# PAPR_02.net
KiCad netlist of a schematic drawn in EAGLE
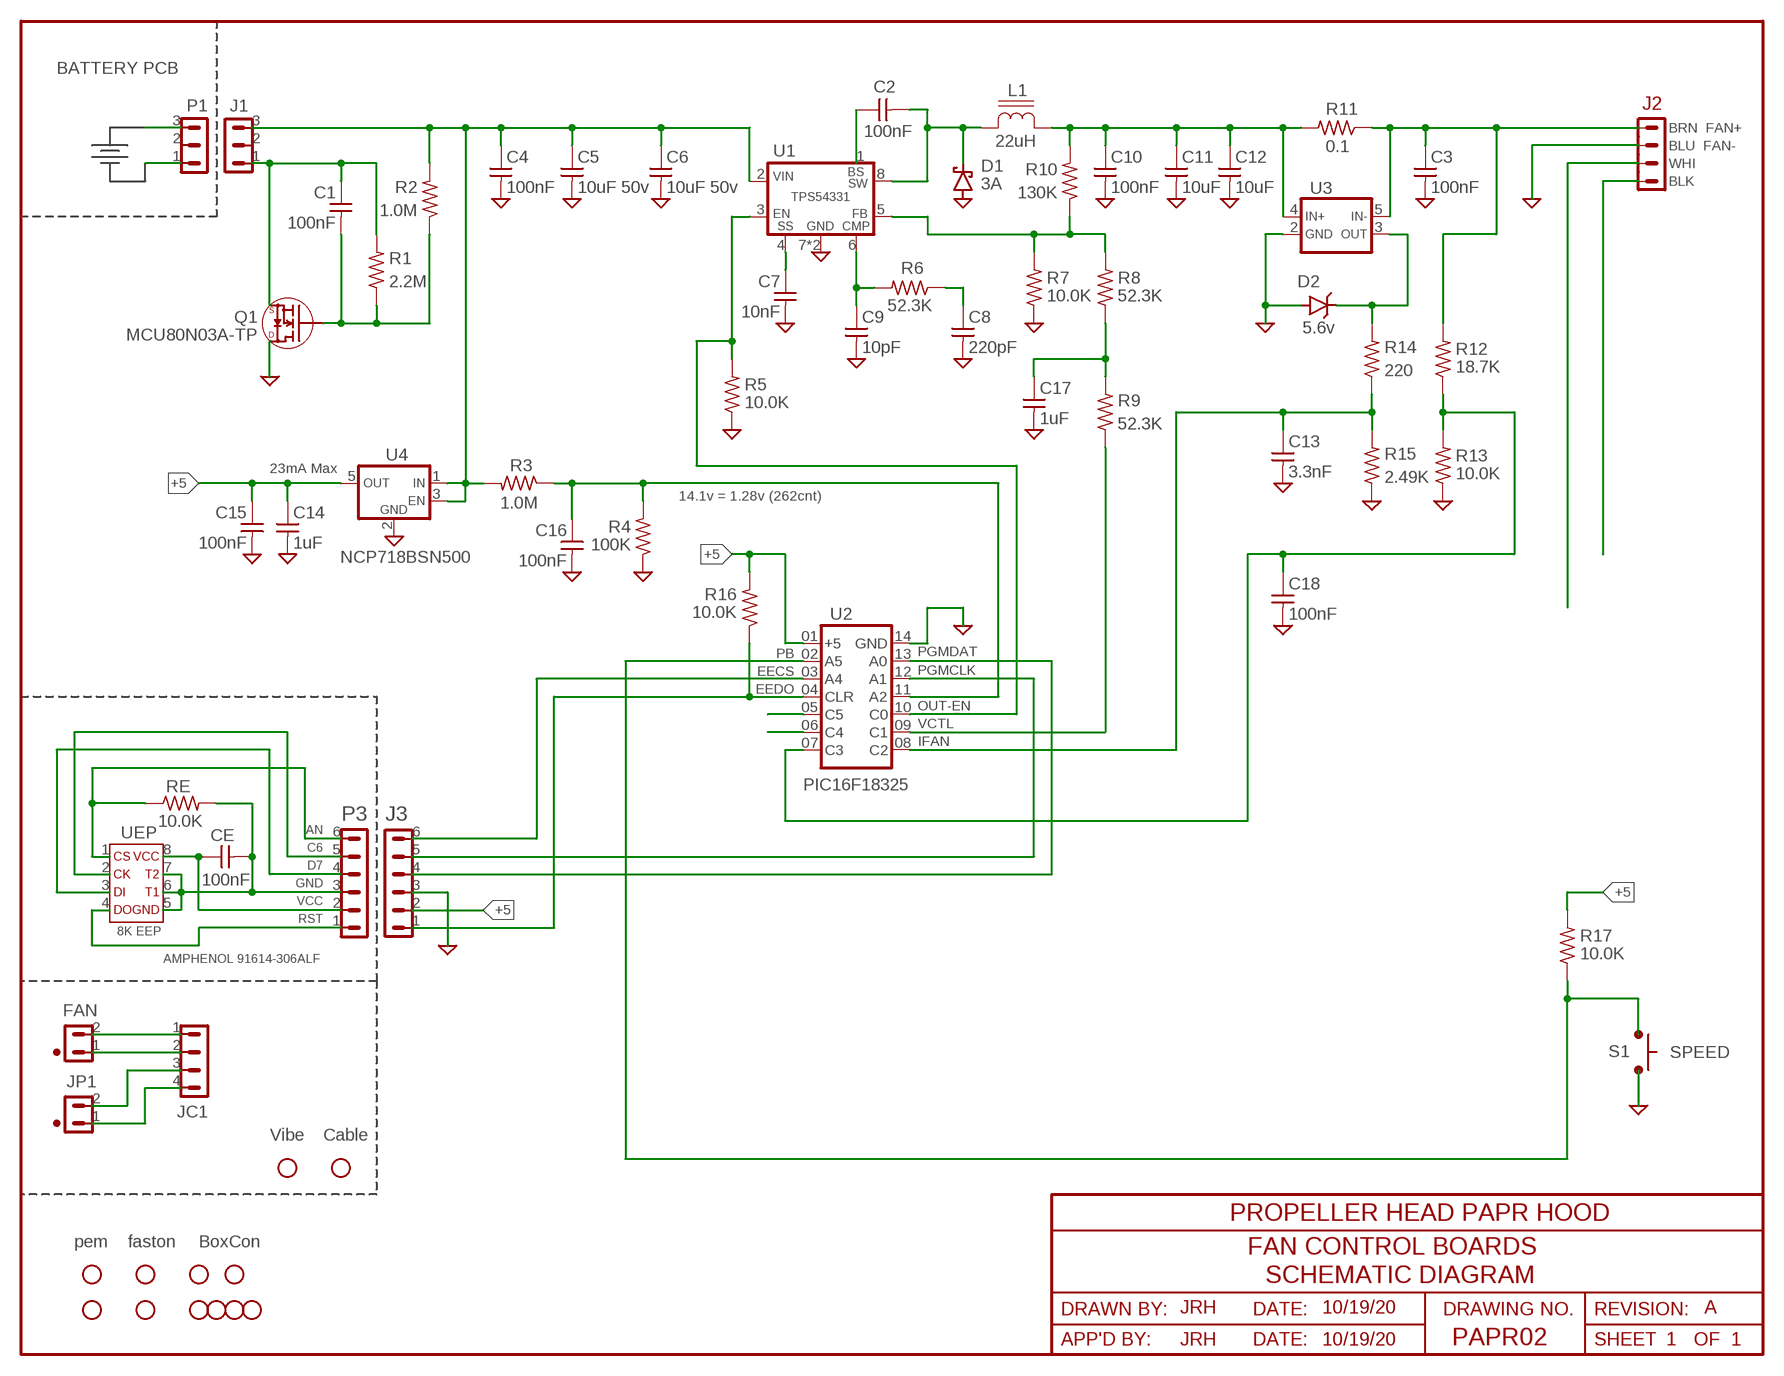
[diagram p0: schematic, sheet 1]

(export (version "E")
  (design (tool "Eeschema 10.0.6"))
  (components
    (comp (ref "BOM1")
      (value "pem")
      (footprint "eagle-import:BOM_ADDER")
      (fields
        (field (name "MFG") "???")
        (field (name "DESC") "PEM Fastener")
        (field (name "MFG_1") "PEM Engineering")
        (field (name "PART_NUMBER") "KF2-440-ET")
        (field (name "PRICE") "0.40")
      )
      (libsource (lib "eagle-import") (part "BOM_ADDER"))
    )
    (comp (ref "BOM2")
      (value "pem")
      (footprint "eagle-import:BOM_ADDER")
      (fields
        (field (name "MFG") "???")
        (field (name "DESC") "PEM Fastener")
        (field (name "MFG_1") "PEM Engineering")
        (field (name "PART_NUMBER") "KF2-440-ET")
        (field (name "PRICE") "0.40")
      )
      (libsource (lib "eagle-import") (part "BOM_ADDER"))
    )
    (comp (ref "BOM3")
      (value "faston")
      (footprint "eagle-import:BOM_ADDER")
      (fields
        (field (name "MFG") "???")
        (field (name "DESC") "Terminal, Faston 0.250")
        (field (name "MFG_1") "Keystone")
        (field (name "PART_NUMBER") "4901")
        (field (name "PRICE") "0.1874")
        (field (name "SUPPLIER") "Digikey 36-4901-ND")
      )
      (libsource (lib "eagle-import") (part "BOM_ADDER"))
    )
    (comp (ref "BOM4")
      (value "faston")
      (footprint "eagle-import:BOM_ADDER")
      (fields
        (field (name "MFG") "???")
        (field (name "DESC") "Terminal, Faston 0.250")
        (field (name "MFG_1") "Keystone")
        (field (name "PART_NUMBER") "4901")
        (field (name "PRICE") "0.1874")
        (field (name "SUPPLIER") "Digikey 36-4901-ND")
      )
      (libsource (lib "eagle-import") (part "BOM_ADDER"))
    )
    (comp (ref "BOM5")
      (value "vibrator")
      (footprint "eagle-import:BOM_ADDER")
      (fields
        (field (name "MFG") "???")
        (field (name "DESC") "Vibrator")
        (field (name "MFG_1") "Jinlong")
        (field (name "PART_NUMBER") "Z6SCAB0061141")
        (field (name "PRICE") "2.657")
        (field (name "SUPPLIER") "Digikey 1670-1021-ND")
      )
      (libsource (lib "eagle-import") (part "BOM_ADDER"))
    )
    (comp (ref "BOM6")
      (value "BoxCon")
      (footprint "eagle-import:BOM_ADDER")
      (fields
        (field (name "MFG") "???")
        (field (name "DESC") "Connector,Circular,4p")
        (field (name "MFG_1") "TE")
        (field (name "PART_NUMBER") "T4070014041-001")
        (field (name "PRICE") "6.9932")
        (field (name "SUPPLIER") "Digikey A126812-ND")
      )
      (libsource (lib "eagle-import") (part "BOM_ADDER"))
    )
    (comp (ref "BOM7")
      (value "Cable")
      (footprint "eagle-import:BOM_ADDER")
      (fields
        (field (name "MFG") "???")
        (field (name "DESC") "Cable,Circular,4p")
        (field (name "MFG_1") "TE")
        (field (name "PART_NUMBER") "1-2273003-1")
        (field (name "PRICE") "10.3224")
        (field (name "SUPPLIER") "Digikey A120949-ND")
      )
      (libsource (lib "eagle-import") (part "BOM_ADDER"))
    )
    (comp (ref "BOM8")
      (value "Plug")
      (footprint "eagle-import:BOM_ADDER")
      (fields
        (field (name "MFG") "???")
        (field (name "DESC") "Plug,4p,MicroMate 3mm c-c")
        (field (name "MFG_1") "TE")
        (field (name "PART_NUMBER") "1445022-4")
        (field (name "PRICE") "0.3464")
        (field (name "SUPPLIER") "Digikey A30260-ND")
      )
      (libsource (lib "eagle-import") (part "BOM_ADDER"))
    )
    (comp (ref "BOM9")
      (value "Pin")
      (footprint "eagle-import:BOM_ADDER")
      (fields
        (field (name "MFG") "???")
        (field (name "DESC") "Terminal,male,MicroMate,gold,30u")
        (field (name "MFG_1") "TE")
        (field (name "PART_NUMBER") "1-794606-1")
        (field (name "PRICE") "0.1049")
        (field (name "SUPPLIER") "Digikey A100439CT-ND")
      )
      (libsource (lib "eagle-import") (part "BOM_ADDER"))
    )
    (comp (ref "BOM10")
      (value "Pin")
      (footprint "eagle-import:BOM_ADDER")
      (fields
        (field (name "MFG") "???")
        (field (name "DESC") "Terminal,male,MicroMate,gold,30u")
        (field (name "MFG_1") "TE")
        (field (name "PART_NUMBER") "1-794606-1")
        (field (name "PRICE") "0.1049")
        (field (name "SUPPLIER") "Digikey A100439CT-ND")
      )
      (libsource (lib "eagle-import") (part "BOM_ADDER"))
    )
    (comp (ref "BOM11")
      (value "Pin")
      (footprint "eagle-import:BOM_ADDER")
      (fields
        (field (name "MFG") "???")
        (field (name "DESC") "Terminal,male,MicroMate,gold,30u")
        (field (name "MFG_1") "TE")
        (field (name "PART_NUMBER") "1-794606-1")
        (field (name "PRICE") "0.1049")
        (field (name "SUPPLIER") "Digikey A100439CT-ND")
      )
      (libsource (lib "eagle-import") (part "BOM_ADDER"))
    )
    (comp (ref "BOM12")
      (value "Pin")
      (footprint "eagle-import:BOM_ADDER")
      (fields
        (field (name "MFG") "???")
        (field (name "DESC") "Terminal,male,MicroMate,gold,30u")
        (field (name "MFG_1") "TE")
        (field (name "PART_NUMBER") "1-794606-1")
        (field (name "PRICE") "0.1049")
        (field (name "SUPPLIER") "Digikey A100439CT-ND")
      )
      (libsource (lib "eagle-import") (part "BOM_ADDER"))
    )
    (comp (ref "C1")
      (value "100nF")
      (footprint "eagle-import:R0805")
      (fields
        (field (name "MFG") "??")
        (field (name "DESC") "Capacitor,100nF,50v, MonoCer,X7R,10%")
        (field (name "MFG_1") "Samsung              AVX")
        (field (name "PART_NUMBER") "CL21B104KBC5PNL             08055C104KAT4A")
        (field (name "SUPPLIER") "Digikey 1276-7000-1-ND    478-10836-1-ND")
      )
      (libsource (lib "eagle-import") (part "C-N0805"))
    )
    (comp (ref "C2")
      (value "100nF")
      (footprint "eagle-import:R0805")
      (fields
        (field (name "MFG") "??")
        (field (name "DESC") "Capacitor,100nF,50v, MonoCer,X7R,10%")
        (field (name "MFG_1") "Samsung              AVX")
        (field (name "PART_NUMBER") "CL21B104KBC5PNL             08055C104KAT4A")
        (field (name "SUPPLIER") "Digikey 1276-7000-1-ND    478-10836-1-ND")
      )
      (libsource (lib "eagle-import") (part "C-N0805"))
    )
    (comp (ref "C3")
      (value "100nF")
      (footprint "eagle-import:R0805")
      (fields
        (field (name "MFG") "??")
        (field (name "DESC") "Capacitor,100nF,50v, MonoCer,X7R,10%")
        (field (name "MFG_1") "Samsung              AVX")
        (field (name "PART_NUMBER") "CL21B104KBC5PNL             08055C104KAT4A")
        (field (name "SUPPLIER") "Digikey 1276-7000-1-ND    478-10836-1-ND")
      )
      (libsource (lib "eagle-import") (part "C-N0805"))
    )
    (comp (ref "C4")
      (value "100nF")
      (footprint "eagle-import:R0805")
      (fields
        (field (name "MFG") "??")
        (field (name "DESC") "Capacitor,100nF,50v, MonoCer,X7R,10%")
        (field (name "MFG_1") "Samsung              AVX")
        (field (name "PART_NUMBER") "CL21B104KBC5PNL             08055C104KAT4A")
        (field (name "SUPPLIER") "Digikey 1276-7000-1-ND    478-10836-1-ND")
      )
      (libsource (lib "eagle-import") (part "C-N0805"))
    )
    (comp (ref "C5")
      (value "10uF 50v")
      (footprint "eagle-import:R1210")
      (fields
        (field (name "MFG") "??")
        (field (name "DESC") "Capacitor,10uF,50v, MonoCer,X7R,10%")
        (field (name "MFG_1") "TDK")
        (field (name "PART_NUMBER") "C3225X7R1H106M250AC")
        (field (name "SUPPLIER") "Digikey 445-14933-1-ND")
      )
      (libsource (lib "eagle-import") (part "C-N1210"))
    )
    (comp (ref "C6")
      (value "10uF 50v")
      (footprint "eagle-import:R1210")
      (fields
        (field (name "MFG") "??")
        (field (name "DESC") "Capacitor,10uF,50v, MonoCer,X7R,10%")
        (field (name "MFG_1") "TDK")
        (field (name "PART_NUMBER") "C3225X7R1H106M250AC")
        (field (name "SUPPLIER") "Digikey 445-14933-1-ND")
      )
      (libsource (lib "eagle-import") (part "C-N1210"))
    )
    (comp (ref "C7")
      (value "10nF")
      (footprint "eagle-import:R0805")
      (fields
        (field (name "MFG") "??")
        (field (name "DESC") "Capacitor,10nF,50v, MonoCer,X7R,10%")
        (field (name "MFG_1") "Samsung              AVX")
        (field (name "PART_NUMBER") "CL21B103KBANNNC        C0805C103K1RAC7210")
        (field (name "SUPPLIER") "Digikey 1276-1015-1-ND")
      )
      (libsource (lib "eagle-import") (part "C-N0805"))
    )
    (comp (ref "C8")
      (value "220pF")
      (footprint "eagle-import:R0805")
      (fields
        (field (name "MFG") "??")
        (field (name "DESC") "Capacitor,220pF,50v, MonoCer,C0G,5%")
        (field (name "MFG_1") "Samsung              Venkel")
        (field (name "PART_NUMBER") "CL21C221JBANNNC         C0805C0G500-221JNE")
        (field (name "SUPPLIER") "Digikey 1276-1164-1-ND")
      )
      (libsource (lib "eagle-import") (part "C-N0805"))
    )
    (comp (ref "C9")
      (value "10pF")
      (footprint "eagle-import:R0805")
      (fields
        (field (name "MFG") "??")
        (field (name "DESC") "Capacitor,10pF,50v, MonoCer,NPO,10%")
        (field (name "MFG_1") "Kemet           Stackpole")
        (field (name "PART_NUMBER") "C0805C100K5GACTU         CML0805C0G100JT50V")
        (field (name "SUPPLIER") "Digikey 399-7975-1-ND")
      )
      (libsource (lib "eagle-import") (part "C-N0805"))
    )
    (comp (ref "C10")
      (value "100nF")
      (footprint "eagle-import:R0805")
      (fields
        (field (name "MFG") "??")
        (field (name "DESC") "Capacitor,100nF,50v, MonoCer,X7R,10%")
        (field (name "MFG_1") "Samsung              AVX")
        (field (name "PART_NUMBER") "CL21B104KBC5PNL             08055C104KAT4A")
        (field (name "SUPPLIER") "Digikey 1276-7000-1-ND    478-10836-1-ND")
      )
      (libsource (lib "eagle-import") (part "C-N0805"))
    )
    (comp (ref "C11")
      (value "10uF")
      (footprint "eagle-import:R1210")
      (fields
        (field (name "MFG") "??")
        (field (name "DESC") "Capacitor,10uF,25v, MonoCer,X7R,10%")
        (field (name "MFG_1") "Samsung        Taiyo Yuden")
        (field (name "PART_NUMBER") "CL32A106KAULNNE         TMK325BJ106KN-T")
        (field (name "SUPPLIER") "Digikey 1276-1854-1-ND       587-5950-1-ND")
      )
      (libsource (lib "eagle-import") (part "C-N1210"))
    )
    (comp (ref "C12")
      (value "10uF")
      (footprint "eagle-import:R1210")
      (fields
        (field (name "MFG") "??")
        (field (name "DESC") "Capacitor,10uF,25v, MonoCer,X7R,10%")
        (field (name "MFG_1") "Samsung        Taiyo Yuden")
        (field (name "PART_NUMBER") "CL32A106KAULNNE         TMK325BJ106KN-T")
        (field (name "SUPPLIER") "Digikey 1276-1854-1-ND       587-5950-1-ND")
      )
      (libsource (lib "eagle-import") (part "C-N1210"))
    )
    (comp (ref "C13")
      (value "3.3nF")
      (footprint "eagle-import:R0805")
      (fields
        (field (name "MFG") "??")
        (field (name "DESC") "Capacitor,3.3nF,50v, MonoCer,X7R,10%")
        (field (name "MFG_1") "Kemet")
        (field (name "PART_NUMBER") "C0805C332K5RACTU")
        (field (name "SUPPLIER") "Digikey 399-1153-1-ND")
      )
      (libsource (lib "eagle-import") (part "C-N0805"))
    )
    (comp (ref "C14")
      (value "1uF")
      (footprint "eagle-import:R0805")
      (fields
        (field (name "MFG") "??")
        (field (name "DESC") "Capacitor,1uF,50v, MonoCer,X7R,10%")
        (field (name "MFG_1") "Samsung             Taiyo Yuden")
        (field (name "PART_NUMBER") "CL21B105KOFNNNG         EMK212B7105KG-T")
        (field (name "SUPPLIER") "Digikey 1276-6471-1-ND")
      )
      (libsource (lib "eagle-import") (part "C-N0805"))
    )
    (comp (ref "C15")
      (value "100nF")
      (footprint "eagle-import:R0805")
      (fields
        (field (name "MFG") "??")
        (field (name "DESC") "Capacitor,100nF,50v, MonoCer,X7R,10%")
        (field (name "MFG_1") "Samsung              AVX")
        (field (name "PART_NUMBER") "CL21B104KBC5PNL             08055C104KAT4A")
        (field (name "SUPPLIER") "Digikey 1276-7000-1-ND    478-10836-1-ND")
      )
      (libsource (lib "eagle-import") (part "C-N0805"))
    )
    (comp (ref "C16")
      (value "100nF")
      (footprint "eagle-import:R0805")
      (fields
        (field (name "MFG") "??")
        (field (name "DESC") "Capacitor,100nF,50v, MonoCer,X7R,10%")
        (field (name "MFG_1") "Samsung              AVX")
        (field (name "PART_NUMBER") "CL21B104KBC5PNL             08055C104KAT4A")
        (field (name "SUPPLIER") "Digikey 1276-7000-1-ND    478-10836-1-ND")
      )
      (libsource (lib "eagle-import") (part "C-N0805"))
    )
    (comp (ref "C17")
      (value "1uF")
      (footprint "eagle-import:R0805")
      (fields
        (field (name "MFG") "??")
        (field (name "DESC") "Capacitor,1uF,50v, MonoCer,X7R,10%")
        (field (name "MFG_1") "Samsung             Taiyo Yuden")
        (field (name "PART_NUMBER") "CL21B105KOFNNNG         EMK212B7105KG-T")
        (field (name "SUPPLIER") "Digikey 1276-6471-1-ND")
      )
      (libsource (lib "eagle-import") (part "C-N0805"))
    )
    (comp (ref "C18")
      (value "100nF")
      (footprint "eagle-import:R0805")
      (fields
        (field (name "MFG") "??")
        (field (name "DESC") "Capacitor,100nF,50v, MonoCer,X7R,10%")
        (field (name "MFG_1") "Samsung              AVX")
        (field (name "PART_NUMBER") "CL21B104KBC5PNL             08055C104KAT4A")
        (field (name "SUPPLIER") "Digikey 1276-7000-1-ND    478-10836-1-ND")
      )
      (libsource (lib "eagle-import") (part "C-N0805"))
    )
    (comp (ref "CE")
      (value "100nF")
      (footprint "eagle-import:R0805")
      (fields
        (field (name "MFG") "??")
        (field (name "DESC") "Capacitor,100nF,50v, MonoCer,X7R,10%")
        (field (name "MFG_1") "Samsung              AVX")
        (field (name "PART_NUMBER") "CL21B104KBC5PNL             08055C104KAT4A")
        (field (name "SUPPLIER") "Digikey 1276-7000-1-ND    478-10836-1-ND")
      )
      (libsource (lib "eagle-import") (part "C-N0805"))
    )
    (comp (ref "D1")
      (value "3A")
      (footprint "eagle-import:SMA")
      (fields
        (field (name "MFG") "??")
        (field (name "DESC") "Diode,3A,40V,Schottky,SMA")
        (field (name "MFG_1") "Diodes Inc        OnSemi         Vishay")
        (field (name "PART_NUMBER") "B340A-13-F          MBRA340T3G          SSA34HE3_A/I")
        (field (name "PRICE") "0.191")
        (field (name "SUPPLIER") "Digikey B340A-FDICT-ND     MBRA340T3GOSCT-ND    SSA34HE3_A/IGICT-ND")
      )
      (libsource (lib "eagle-import") (part "DIODES-1A"))
    )
    (comp (ref "D2")
      (value "5.6v")
      (footprint "eagle-import:SOT23-3")
      (fields
        (field (name "MFG") "NXP")
        (field (name "PART_NUMBER") "BZX84-BxVx")
        (field (name "DESC") "Zener,5.6v,250mW,SOT23-3")
        (field (name "MFG_1") "On Semi")
        (field (name "PART_NUMBER_1") "SZBZX84-C5V6LT1G")
        (field (name "PRICE") "0.118")
        (field (name "SUPPLIER") "Digikey SZBZX84C5V6LT1GOSCT-ND")
      )
      (libsource (lib "eagle-import") (part "ZENER3"))
    )
    (comp (ref "FAN")
      (value "Fan_Hdr")
      (footprint "eagle-import:641215-2")
      (fields (field (name "MFG") "Tyco") (field (name "PART_NUMBER") "641215-2"))
      (libsource (lib "eagle-import") (part "HDR02V"))
    )
    (comp (ref "J1")
      (value "bat")
      (footprint "eagle-import:1746142")
      (fields (field (name "MFG") "TI") (field (name "PART_NUMBER") "1745142-1"))
      (libsource (lib "eagle-import") (part "HDR03_17"))
    )
    (comp (ref "J2-BLK")
      (value "WIRE-HDRS200")
      (footprint "eagle-import:PADS200")
      (fields (field (name "MFG") "??"))
      (libsource (lib "eagle-import") (part "WIRE-HDRS200"))
    )
    (comp (ref "J2-BLU")
      (value "WIRE-HDRS200")
      (footprint "eagle-import:PADS200")
      (fields (field (name "MFG") "??"))
      (libsource (lib "eagle-import") (part "WIRE-HDRS200"))
    )
    (comp (ref "J2-BRN")
      (value "WIRE-HDRS200")
      (footprint "eagle-import:PADS200")
      (fields (field (name "MFG") "??"))
      (libsource (lib "eagle-import") (part "WIRE-HDRS200"))
    )
    (comp (ref "J2-WHI")
      (value "WIRE-HDRS200")
      (footprint "eagle-import:PADS200")
      (fields (field (name "MFG") "??"))
      (libsource (lib "eagle-import") (part "WIRE-HDRS200"))
    )
    (comp (ref "J3")
      (value "6p")
      (footprint "eagle-import:J06P")
      (fields
        (field (name "MFG") "??")
        (field (name "DESC") "Header,6p,thru,gold,8.89mm")
        (field (name "MFG_1") "Samtec")
        (field (name "PART_NUMBER") "MTSW-106-22-G-S-350")
        (field (name "PRICE") "0.750")
        (field (name "SUPPLIER") "Digikey MTSW-106-22-G-S-350-ND")
      )
      (libsource (lib "eagle-import") (part "HDR06R"))
    )
    (comp (ref "JC1")
      (value "Cable_Termination")
      (footprint "eagle-import:B4P-VH")
      (fields (field (name "MFG") "JST") (field (name "PART_NUMBER") "B4P-VH"))
      (libsource (lib "eagle-import") (part "HDR04_JST_B4P-VH"))
    )
    (comp (ref "JP1")
      (value "Spare")
      (footprint "eagle-import:641215-2")
      (fields (field (name "MFG") "Tyco") (field (name "PART_NUMBER") "641215-2"))
      (libsource (lib "eagle-import") (part "HDR02V"))
    )
    (comp (ref "L1")
      (value "22uH")
      (footprint "eagle-import:SRU1048")
      (fields
        (field (name "MFG") "Bourns")
        (field (name "PART_NUMBER") "SDR1048-")
        (field (name "PRICE") "0.6756")
        (field (name "SUPPLIER") "Digikey SRU1048-220YCT-ND")
      )
      (libsource (lib "eagle-import") (part "COIL1048"))
    )
    (comp (ref "P1")
      (value "bat")
      (footprint "eagle-import:1746142M")
      (fields (field (name "MFG") "TI") (field (name "PART_NUMBER") "1745142-1 Mate"))
      (libsource (lib "eagle-import") (part "HDR03_17M"))
    )
    (comp (ref "P3")
      (value "6p plug")
      (footprint "eagle-import:J06P")
      (fields (field (name "MFG") "??"))
      (libsource (lib "eagle-import") (part "HDR06R"))
    )
    (comp (ref "Q1")
      (value "MCU80N03A-TP")
      (footprint "eagle-import:TO252")
      (fields
        (field (name "MFG") "??")
        (field (name "DESC") "MOSFET,N-Ch,30v,<18m")
        (field (name "MFG_1") "MCC                  Diodes Inc           On Semi")
        (field (name "PART_NUMBER") "MCU80N03A-TP           DMG4800LK3-13             NTD4969NT4G")
        (field (name "PRICE") "0.40")
        (field (name "SUPPLIER") "Digikey 353-MCU80N03A-TPCT-ND")
      )
      (libsource (lib "eagle-import") (part "IGFETNM"))
    )
    (comp (ref "R1")
      (value "2.2M")
      (footprint "eagle-import:R0805")
      (fields
        (field (name "MFG") "Vishay")
        (field (name "PART_NUMBER") "CRCW0805xxxFKEA")
        (field (name "DESC") "Resistor,2.2M,1/8w,1%")
        (field (name "MFG_1") "Stackpole             Vishay")
        (field (name "PART_NUMBER_1") "RMCF0805FT2M21          CRCW08052M20FKEA")
        (field (name "SUPPLIER") "Digikey RMCF0805FT2M21CT-ND")
      )
      (libsource (lib "eagle-import") (part "R0805"))
    )
    (comp (ref "R2")
      (value "1.0M")
      (footprint "eagle-import:R0805")
      (fields
        (field (name "MFG") "Vishay")
        (field (name "PART_NUMBER") "CRCW0805xxxFKEA")
        (field (name "DESC") "Resistor,1.0M,1/8w,1%")
        (field (name "MFG_1") "Stackpole              KOA Speer")
        (field (name "PART_NUMBER_1") "RMCF0805FG1M00          RK73H2ATTD1004F")
        (field (name "SUPPLIER") "Digikey RMCF0805FG1M00CT-ND       2019-RK73H2ATTD1004FCT-ND")
      )
      (libsource (lib "eagle-import") (part "R0805"))
    )
    (comp (ref "R3")
      (value "1.0M")
      (footprint "eagle-import:R0805")
      (fields
        (field (name "MFG") "Vishay")
        (field (name "PART_NUMBER") "CRCW0805xxxFKEA")
        (field (name "DESC") "Resistor,1.0M,1/8w,1%")
        (field (name "MFG_1") "Stackpole             Vishay")
        (field (name "PART_NUMBER_1") "RMCF0805FT2M21          CRCW08052M20FKEA")
        (field (name "SUPPLIER") "Digikey RMCF0805FT2M21CT-ND       541-2.20MCCT-ND")
      )
      (libsource (lib "eagle-import") (part "R0805"))
    )
    (comp (ref "R4")
      (value "100K")
      (footprint "eagle-import:R0805")
      (fields
        (field (name "MFG") "Vishay")
        (field (name "PART_NUMBER") "CRCW0805xxxFKEA")
        (field (name "DESC") "Resistor,100K,1/8w,1%")
        (field (name "MFG_1") "Stackpole             KOA Speer")
        (field (name "PART_NUMBER_1") "RMCF0805FG100K          RK73H2ATTD1003F")
        (field (name "SUPPLIER") "Digikey RMCF0805FT100KTR-ND")
      )
      (libsource (lib "eagle-import") (part "R0805"))
    )
    (comp (ref "R5")
      (value "10.0K")
      (footprint "eagle-import:R0805")
      (fields
        (field (name "MFG") "Vishay")
        (field (name "PART_NUMBER") "CRCW0805xxxFKEA")
        (field (name "DESC") "Resistor,10.0K,1/8w,1%")
        (field (name "MFG_1") "Stackpole             KOA Speer")
        (field (name "PART_NUMBER_1") "RMCF0805FT10K0          RK73H2ATTD1002F")
        (field (name "SUPPLIER") "Digikey RMCF0805FT10K0CT-ND")
      )
      (libsource (lib "eagle-import") (part "R0805"))
    )
    (comp (ref "R6")
      (value "52.3K")
      (footprint "eagle-import:R0805")
      (fields
        (field (name "MFG") "Vishay")
        (field (name "PART_NUMBER") "CRCW0805xxxFKEA")
        (field (name "DESC") "Resistor,52.3K,1/8w,1%")
        (field (name "MFG_1") "Yageo          Vishay")
        (field (name "PART_NUMBER_1") "RC0805FR-0752K3L        CRCW080552K3FKEA")
        (field (name "SUPPLIER") "Digikey 311-52.3KCRCT-ND")
      )
      (libsource (lib "eagle-import") (part "R0805"))
    )
    (comp (ref "R7")
      (value "10.0K")
      (footprint "eagle-import:R0805")
      (fields
        (field (name "MFG") "Vishay")
        (field (name "PART_NUMBER") "CRCW0805xxxFKEA")
        (field (name "DESC") "Resistor,10.0K,1/8w,1%")
        (field (name "MFG_1") "Stackpole             KOA Speer")
        (field (name "PART_NUMBER_1") "RMCF0805FT10K0          RK73H2ATTD1002F")
        (field (name "SUPPLIER") "Digikey RMCF0805FT10K0CT-ND")
      )
      (libsource (lib "eagle-import") (part "R0805"))
    )
    (comp (ref "R8")
      (value "52.3K")
      (footprint "eagle-import:R0805")
      (fields
        (field (name "MFG") "Vishay")
        (field (name "PART_NUMBER") "CRCW0805xxxFKEA")
        (field (name "DESC") "Resistor,52.3K,1/8w,1%")
        (field (name "MFG_1") "Yageo          Vishay")
        (field (name "PART_NUMBER_1") "RC0805FR-0752K3L        CRCW080552K3FKEA")
        (field (name "SUPPLIER") "Digikey 311-52.3KCRCT-ND")
      )
      (libsource (lib "eagle-import") (part "R0805"))
    )
    (comp (ref "R9")
      (value "52.3K")
      (footprint "eagle-import:R0805")
      (fields
        (field (name "MFG") "Vishay")
        (field (name "PART_NUMBER") "CRCW0805xxxFKEA")
        (field (name "DESC") "Resistor,52.3K,1/8w,1%")
        (field (name "MFG_1") "Yageo          Vishay")
        (field (name "PART_NUMBER_1") "RC0805FR-0752K3L        CRCW080552K3FKEA")
        (field (name "SUPPLIER") "Digikey 311-52.3KCRCT-ND")
      )
      (libsource (lib "eagle-import") (part "R0805"))
    )
    (comp (ref "R10")
      (value "130K")
      (footprint "eagle-import:R0805")
      (fields
        (field (name "MFG") "Vishay")
        (field (name "PART_NUMBER") "CRCW0805xxxFKEA")
        (field (name "DESC") "Resistor,130K,1/8w,1%")
        (field (name "MFG_1") "KOA Speer         Yageo")
        (field (name "PART_NUMBER_1") "RK73H2ATTD1303F         RC0805FR-07130KL")
        (field (name "SUPPLIER") "Digikey 2019-RK73H2ATTD1303FCT-ND")
      )
      (libsource (lib "eagle-import") (part "R0805"))
    )
    (comp (ref "R11")
      (value "0.1")
      (footprint "eagle-import:R2512")
      (fields
        (field (name "MFG") "Vishay")
        (field (name "PART_NUMBER") "CRCW2512xxxFKEA")
        (field (name "DESC") "Resistor,0.1,2w,1%")
        (field (name "MFG_1") "Stackpole")
        (field (name "PART_NUMBER_1") "CSRN2512FTR100")
        (field (name "SUPPLIER") "Digikey CSRN2512FTR100CT-ND")
      )
      (libsource (lib "eagle-import") (part "R2512"))
    )
    (comp (ref "R12")
      (value "18.7K")
      (footprint "eagle-import:R0805")
      (fields
        (field (name "MFG") "Vishay")
        (field (name "PART_NUMBER") "CRCW0805xxxFKEA")
        (field (name "DESC") "Resistor,18.7K,1/8w,1%")
        (field (name "MFG_1") "Stackpole             Yageo")
        (field (name "PART_NUMBER_1") "RMCF0805FT18K7          RC0805FR0718K7L")
        (field (name "SUPPLIER") "Digikey RMCF0805FT18K7CT-ND")
      )
      (libsource (lib "eagle-import") (part "R0805"))
    )
    (comp (ref "R13")
      (value "10.0K")
      (footprint "eagle-import:R0805")
      (fields
        (field (name "MFG") "Vishay")
        (field (name "PART_NUMBER") "CRCW0805xxxFKEA")
        (field (name "DESC") "Resistor,10.0K,1/8w,1%")
        (field (name "MFG_1") "Stackpole             KOA Speer")
        (field (name "PART_NUMBER_1") "RMCF0805FT10K0          RK73H2ATTD1002F")
        (field (name "SUPPLIER") "Digikey RMCF0805FT10K0CT-ND")
      )
      (libsource (lib "eagle-import") (part "R0805"))
    )
    (comp (ref "R14")
      (value "220")
      (footprint "eagle-import:R0805")
      (fields
        (field (name "MFG") "Vishay")
        (field (name "PART_NUMBER") "CRCW0805xxxFKEA")
        (field (name "DESC") "Resistor,220,1/8w,1%")
        (field (name "MFG_1") "Stackpole             KOA Speer")
        (field (name "PART_NUMBER_1") "RMCF0805FT220R          RK73H2ATTD2200F")
        (field (name "SUPPLIER") "Digikey RMCF0805FT220RCT-ND")
      )
      (libsource (lib "eagle-import") (part "R0805"))
    )
    (comp (ref "R15")
      (value "2.49K")
      (footprint "eagle-import:R0805")
      (fields
        (field (name "MFG") "Vishay")
        (field (name "PART_NUMBER") "CRCW0805xxxFKEA")
        (field (name "DESC") "Resistor,2.49K,1/8w,1%")
        (field (name "MFG_1") "Stackpole             Vishay")
        (field (name "PART_NUMBER_1") "RMCF0805FT2K49          CRCW08052K49FKEA")
        (field (name "SUPPLIER") "Digikey RMCF0805FT2K49CT-ND")
      )
      (libsource (lib "eagle-import") (part "R0805"))
    )
    (comp (ref "R16")
      (value "10.0K")
      (footprint "eagle-import:R0805")
      (fields
        (field (name "MFG") "Vishay")
        (field (name "PART_NUMBER") "CRCW0805xxxFKEA")
        (field (name "DESC") "Resistor,10.0K,1/8w,1%")
        (field (name "MFG_1") "Stackpole             KOA Speer")
        (field (name "PART_NUMBER_1") "RMCF0805FT10K0          RK73H2ATTD1002F")
        (field (name "SUPPLIER") "Digikey RMCF0805FT10K0CT-ND")
      )
      (libsource (lib "eagle-import") (part "R0805"))
    )
    (comp (ref "R17")
      (value "10.0K")
      (footprint "eagle-import:R0805")
      (fields
        (field (name "MFG") "Vishay")
        (field (name "PART_NUMBER") "CRCW0805xxxFKEA")
        (field (name "DESC") "Resistor,10.0K,1/8w,1%")
        (field (name "MFG_1") "Stackpole             KOA Speer")
        (field (name "PART_NUMBER_1") "RMCF0805FT10K0          RK73H2ATTD1002F")
        (field (name "SUPPLIER") "Digikey RMCF0805FT10K0CT-ND")
      )
      (libsource (lib "eagle-import") (part "R0805"))
    )
    (comp (ref "RE")
      (value "10.0K")
      (footprint "eagle-import:R0805")
      (fields
        (field (name "MFG") "Vishay")
        (field (name "PART_NUMBER") "CRCW0805xxxFKEA")
        (field (name "DESC") "Resistor,10.0K,1/8w,1%")
        (field (name "MFG_1") "Stackpole             KOA Speer")
        (field (name "PART_NUMBER_1") "RMCF0805FT10K0          RK73H2ATTD1002F")
        (field (name "SUPPLIER") "Digikey RMCF0805FT10K0CT-ND")
      )
      (libsource (lib "eagle-import") (part "R0805"))
    )
    (comp (ref "S1")
      (value "SPEED")
      (footprint "eagle-import:EVQ-P7C01P")
      (fields (field (name "MFG") "Panasonic") (field (name "PART_NUMBER") "EVQ-P7C01P"))
      (libsource (lib "eagle-import") (part "PUSHBUTTONQ"))
    )
    (comp (ref "U1")
      (value "TPS54331")
      (footprint "eagle-import:SO08PW")
      (fields
        (field (name "MFG") "TI")
        (field (name "PART_NUMBER") "TPS54331DDAR")
        (field (name "PRICE") "1.352")
      )
      (libsource (lib "eagle-import") (part "TPS54331DDAR"))
    )
    (comp (ref "U2")
      (value "PIC16F18325")
      (footprint "eagle-import:SOIC14")
      (fields
        (field (name "MFG") "Microchip")
        (field (name "PART_NUMBER") "PIC16F616-I/SL")
        (field (name "PART_NUMBER_1") "PIC16F18325-I/SL")
        (field (name "SUPPLIER") "Digikey PIC16F18325-I/SL-ND")
      )
      (libsource (lib "eagle-import") (part "PIC16F616/SL-I"))
    )
    (comp (ref "U3")
      (value "ZXCT1010")
      (footprint "eagle-import:SOT23-5")
      (fields (field (name "MFG") "DiodesInc") (field (name "PART_NUMBER") "ZXCT1010E5TA"))
      (libsource (lib "eagle-import") (part "ZXCT1010E5TA"))
    )
    (comp (ref "U4")
      (value "NCP718BSN500")
      (footprint "eagle-import:SOT23-5")
      (fields
        (field (name "MFG") "T.I.")
        (field (name "PART_NUMBER") "LP2981-50DBVR or BVT")
        (field (name "DESC") "Regulator,LoQ,5.0v,25vIn")
        (field (name "MFG_1") "On Semi")
        (field (name "PART_NUMBER_1") "NCP718BSN500T1G")
        (field (name "SUPPLIER") "Digikey NCP718BSN500T1GOSCT-ND")
      )
      (libsource (lib "eagle-import") (part "LP2981AIM"))
    )
    (comp (ref "UEP")
      (value "4K EEP")
      (footprint "eagle-import:SO08")
      (fields (field (name "MFG") "ROHM Semi") (field (name "PART_NUMBER") "BR93H76RFJ-2CE"))
      (libsource (lib "eagle-import") (part "BR93H76RFJ-2CE"))
    )
  )
  (nets
    (net (code "1") (name "+5") (class "Default")
      (node (ref "C14") (pin "1") (pinfunction "1_1") (pintype "passive"))
      (node (ref "C15") (pin "1") (pinfunction "1_1") (pintype "passive"))
      (node (ref "J3") (pin "2") (pinfunction "2_2") (pintype "passive"))
      (node (ref "R16") (pin "1") (pinfunction "1_1") (pintype "passive"))
      (node (ref "R17") (pin "1") (pinfunction "1_1") (pintype "passive"))
      (node (ref "U2") (pin "01") (pinfunction "VCC_01") (pintype "input"))
      (node (ref "U4") (pin "5") (pinfunction "OUT_5") (pintype "output"))
    )
    (net (code "2") (name "/EECS") (class "Default")
      (node (ref "J3") (pin "6") (pinfunction "6_6") (pintype "passive"))
      (node (ref "U2") (pin "03") (pinfunction "A4_03") (pintype "bidirectional"))
    )
    (net (code "3") (name "/EEDO") (class "Default")
      (node (ref "J3") (pin "1") (pinfunction "1_1") (pintype "passive"))
      (node (ref "R16") (pin "2") (pinfunction "2_2") (pintype "passive"))
      (node (ref "U2") (pin "04") (pinfunction "CLR_04") (pintype "input"))
    )
    (net (code "4") (name "/IFAN") (class "Default")
      (node (ref "C13") (pin "1") (pinfunction "1_1") (pintype "passive"))
      (node (ref "R14") (pin "2") (pinfunction "2_2") (pintype "passive"))
      (node (ref "R15") (pin "1") (pinfunction "1_1") (pintype "passive"))
      (node (ref "U2") (pin "08") (pinfunction "C2_08") (pintype "bidirectional"))
    )
    (net (code "5") (name "/OUT-EN") (class "Default")
      (node (ref "R5") (pin "1") (pinfunction "1_1") (pintype "passive"))
      (node (ref "U1") (pin "3") (pinfunction "EN_3") (pintype "input"))
      (node (ref "U2") (pin "10") (pinfunction "C0_10") (pintype "bidirectional"))
    )
    (net (code "6") (name "/PB") (class "Default")
      (node (ref "R17") (pin "2") (pinfunction "2_2") (pintype "passive"))
      (node (ref "S1") (pin "3") (pinfunction "2_3") (pintype "passive"))
      (node (ref "S1") (pin "4") (pinfunction "2_4") (pintype "passive"))
      (node (ref "U2") (pin "02") (pinfunction "A5_02") (pintype "bidirectional"))
    )
    (net (code "7") (name "/PGMCLK") (class "Default")
      (node (ref "J3") (pin "5") (pinfunction "5_5") (pintype "passive"))
      (node (ref "U2") (pin "12") (pinfunction "A1_12") (pintype "bidirectional"))
    )
    (net (code "8") (name "/PGMDAT") (class "Default")
      (node (ref "J3") (pin "4") (pinfunction "4_4") (pintype "passive"))
      (node (ref "U2") (pin "13") (pinfunction "A0_13") (pintype "bidirectional"))
    )
    (net (code "9") (name "/VCTL") (class "Default")
      (node (ref "R9") (pin "2") (pinfunction "2_2") (pintype "passive"))
      (node (ref "U2") (pin "09") (pinfunction "C1_09") (pintype "bidirectional"))
    )
    (net (code "10") (name "GND") (class "Default")
      (node (ref "C10") (pin "2") (pinfunction "2_2") (pintype "passive"))
      (node (ref "C11") (pin "2") (pinfunction "2_2") (pintype "passive"))
      (node (ref "C12") (pin "2") (pinfunction "2_2") (pintype "passive"))
      (node (ref "C13") (pin "2") (pinfunction "2_2") (pintype "passive"))
      (node (ref "C14") (pin "2") (pinfunction "2_2") (pintype "passive"))
      (node (ref "C15") (pin "2") (pinfunction "2_2") (pintype "passive"))
      (node (ref "C16") (pin "2") (pinfunction "2_2") (pintype "passive"))
      (node (ref "C17") (pin "2") (pinfunction "2_2") (pintype "passive"))
      (node (ref "C18") (pin "2") (pinfunction "2_2") (pintype "passive"))
      (node (ref "C3") (pin "2") (pinfunction "2_2") (pintype "passive"))
      (node (ref "C4") (pin "2") (pinfunction "2_2") (pintype "passive"))
      (node (ref "C5") (pin "2") (pinfunction "2_2") (pintype "passive"))
      (node (ref "C6") (pin "2") (pinfunction "2_2") (pintype "passive"))
      (node (ref "C7") (pin "2") (pinfunction "2_2") (pintype "passive"))
      (node (ref "C8") (pin "2") (pinfunction "2_2") (pintype "passive"))
      (node (ref "C9") (pin "2") (pinfunction "2_2") (pintype "passive"))
      (node (ref "D1") (pin "A") (pinfunction "A_A") (pintype "passive"))
      (node (ref "D2") (pin "1") (pinfunction "A_1") (pintype "passive"))
      (node (ref "J2-BLU") (pin "1") (pinfunction "1_1") (pintype "passive"))
      (node (ref "J3") (pin "3") (pinfunction "3_3") (pintype "passive"))
      (node (ref "Q1") (pin "3") (pinfunction "D_3") (pintype "passive"))
      (node (ref "R13") (pin "2") (pinfunction "2_2") (pintype "passive"))
      (node (ref "R15") (pin "2") (pinfunction "2_2") (pintype "passive"))
      (node (ref "R4") (pin "2") (pinfunction "2_2") (pintype "passive"))
      (node (ref "R5") (pin "2") (pinfunction "2_2") (pintype "passive"))
      (node (ref "R7") (pin "2") (pinfunction "2_2") (pintype "passive"))
      (node (ref "S1") (pin "1") (pinfunction "1_1") (pintype "passive"))
      (node (ref "S1") (pin "2") (pinfunction "1_2") (pintype "passive"))
      (node (ref "U1") (pin "7") (pinfunction "GND_7") (pintype "input"))
      (node (ref "U1") (pin "9") (pinfunction "GND_9") (pintype "input"))
      (node (ref "U2") (pin "14") (pinfunction "GND_14") (pintype "input"))
      (node (ref "U3") (pin "2") (pinfunction "GND_2") (pintype "input"))
      (node (ref "U4") (pin "2") (pinfunction "GND_2") (pintype "input"))
    )
    (net (code "11") (name "Net-(C8-Pad1)") (class "Default")
      (node (ref "C8") (pin "1") (pinfunction "1_1") (pintype "passive"))
      (node (ref "R6") (pin "2") (pinfunction "2_2") (pintype "passive"))
    )
    (net (code "12") (name "Net-(C17-Pad1)") (class "Default")
      (node (ref "C17") (pin "1") (pinfunction "1_1") (pintype "passive"))
      (node (ref "R8") (pin "2") (pinfunction "2_2") (pintype "passive"))
      (node (ref "R9") (pin "1") (pinfunction "1_1") (pintype "passive"))
    )
    (net (code "13") (name "Net-(D2-C)") (class "Default")
      (node (ref "D2") (pin "3") (pinfunction "C_3") (pintype "passive"))
      (node (ref "R14") (pin "1") (pinfunction "1_1") (pintype "passive"))
      (node (ref "U3") (pin "3") (pinfunction "OUT_3") (pintype "input"))
    )
    (net (code "14") (name "Net-(FAN-Pad1)") (class "Default")
      (node (ref "FAN") (pin "1") (pinfunction "1_1") (pintype "passive"))
      (node (ref "JC1") (pin "2") (pinfunction "2_2") (pintype "passive"))
    )
    (net (code "15") (name "Net-(FAN-Pad2)") (class "Default")
      (node (ref "FAN") (pin "2") (pinfunction "2_2") (pintype "passive"))
      (node (ref "JC1") (pin "1") (pinfunction "1_1") (pintype "passive"))
    )
    (net (code "16") (name "Net-(JC1-Pad3)") (class "Default")
      (node (ref "JC1") (pin "3") (pinfunction "3_3") (pintype "passive"))
      (node (ref "JP1") (pin "2") (pinfunction "2_2") (pintype "passive"))
    )
    (net (code "17") (name "Net-(JC1-Pad4)") (class "Default")
      (node (ref "JC1") (pin "4") (pinfunction "4_4") (pintype "passive"))
      (node (ref "JP1") (pin "1") (pinfunction "1_1") (pintype "passive"))
    )
    (net (code "18") (name "Net-(Q1-G)") (class "Default")
      (node (ref "C1") (pin "2") (pinfunction "2_2") (pintype "passive"))
      (node (ref "Q1") (pin "1") (pinfunction "G_1") (pintype "passive"))
      (node (ref "R1") (pin "2") (pinfunction "2_2") (pintype "passive"))
      (node (ref "R2") (pin "2") (pinfunction "2_2") (pintype "passive"))
    )
    (net (code "19") (name "Net-(Q1-S)") (class "Default")
      (node (ref "C1") (pin "1") (pinfunction "1_1") (pintype "passive"))
      (node (ref "J1") (pin "1") (pinfunction "1_1") (pintype "passive"))
      (node (ref "Q1") (pin "2") (pinfunction "S_2") (pintype "passive"))
      (node (ref "R1") (pin "1") (pinfunction "1_1") (pintype "passive"))
    )
    (net (code "20") (name "Net-(U1-BS)") (class "Default")
      (node (ref "C2") (pin "1") (pinfunction "1_1") (pintype "passive"))
      (node (ref "U1") (pin "1") (pinfunction "BS_1") (pintype "input"))
    )
    (net (code "21") (name "Net-(U1-CMP)") (class "Default")
      (node (ref "C9") (pin "1") (pinfunction "1_1") (pintype "passive"))
      (node (ref "R6") (pin "1") (pinfunction "1_1") (pintype "passive"))
      (node (ref "U1") (pin "6") (pinfunction "CMP_6") (pintype "input"))
    )
    (net (code "22") (name "Net-(U1-FB)") (class "Default")
      (node (ref "R10") (pin "2") (pinfunction "2_2") (pintype "passive"))
      (node (ref "R7") (pin "1") (pinfunction "1_1") (pintype "passive"))
      (node (ref "R8") (pin "1") (pinfunction "1_1") (pintype "passive"))
      (node (ref "U1") (pin "5") (pinfunction "FB_5") (pintype "input"))
    )
    (net (code "23") (name "Net-(U1-SS)") (class "Default")
      (node (ref "C7") (pin "1") (pinfunction "1_1") (pintype "passive"))
      (node (ref "U1") (pin "4") (pinfunction "SS_4") (pintype "input"))
    )
    (net (code "24") (name "Net-(U1-SW)") (class "Default")
      (node (ref "C2") (pin "2") (pinfunction "2_2") (pintype "passive"))
      (node (ref "D1") (pin "C") (pinfunction "C_C") (pintype "passive"))
      (node (ref "L1") (pin "1") (pinfunction "1_1") (pintype "passive"))
      (node (ref "U1") (pin "8") (pinfunction "SW_8") (pintype "output"))
    )
    (net (code "25") (name "Net-(U1-VIN)") (class "Default")
      (node (ref "C4") (pin "1") (pinfunction "1_1") (pintype "passive"))
      (node (ref "C5") (pin "1") (pinfunction "1_1") (pintype "passive"))
      (node (ref "C6") (pin "1") (pinfunction "1_1") (pintype "passive"))
      (node (ref "J1") (pin "3") (pinfunction "3_3") (pintype "passive"))
      (node (ref "R2") (pin "1") (pinfunction "1_1") (pintype "passive"))
      (node (ref "R3") (pin "1") (pinfunction "1_1") (pintype "passive"))
      (node (ref "U1") (pin "2") (pinfunction "VIN_2") (pintype "input"))
      (node (ref "U4") (pin "1") (pinfunction "IN_1") (pintype "input"))
      (node (ref "U4") (pin "3") (pinfunction "EN_3") (pintype "passive"))
    )
    (net (code "26") (name "Net-(U2-A2)") (class "Default")
      (node (ref "C16") (pin "1") (pinfunction "1_1") (pintype "passive"))
      (node (ref "R3") (pin "2") (pinfunction "2_2") (pintype "passive"))
      (node (ref "R4") (pin "1") (pinfunction "1_1") (pintype "passive"))
      (node (ref "U2") (pin "11") (pinfunction "A2_11") (pintype "bidirectional"))
    )
    (net (code "27") (name "Net-(U2-C3)") (class "Default")
      (node (ref "C18") (pin "1") (pinfunction "1_1") (pintype "passive"))
      (node (ref "R12") (pin "2") (pinfunction "2_2") (pintype "passive"))
      (node (ref "R13") (pin "1") (pinfunction "1_1") (pintype "passive"))
      (node (ref "U2") (pin "07") (pinfunction "C3_07") (pintype "bidirectional"))
    )
    (net (code "28") (name "Net-(U3-IN+)") (class "Default")
      (node (ref "C10") (pin "1") (pinfunction "1_1") (pintype "passive"))
      (node (ref "C11") (pin "1") (pinfunction "1_1") (pintype "passive"))
      (node (ref "C12") (pin "1") (pinfunction "1_1") (pintype "passive"))
      (node (ref "L1") (pin "2") (pinfunction "2_2") (pintype "passive"))
      (node (ref "R10") (pin "1") (pinfunction "1_1") (pintype "passive"))
      (node (ref "R11") (pin "1") (pinfunction "1_1") (pintype "passive"))
      (node (ref "U3") (pin "4") (pinfunction "IN+_4") (pintype "input"))
    )
    (net (code "29") (name "Net-(U3-IN-)") (class "Default")
      (node (ref "C3") (pin "1") (pinfunction "1_1") (pintype "passive"))
      (node (ref "J2-BRN") (pin "1") (pinfunction "1_1") (pintype "passive"))
      (node (ref "R11") (pin "2") (pinfunction "2_2") (pintype "passive"))
      (node (ref "R12") (pin "1") (pinfunction "1_1") (pintype "passive"))
      (node (ref "U3") (pin "5") (pinfunction "IN-_5") (pintype "input"))
    )
    (net (code "30") (name "Net-(UEP-CS)") (class "Default")
      (node (ref "P3") (pin "6") (pinfunction "6_6") (pintype "passive"))
      (node (ref "RE") (pin "2") (pinfunction "2_2") (pintype "passive"))
      (node (ref "UEP") (pin "1") (pinfunction "CS_1") (pintype "bidirectional"))
    )
    (net (code "31") (name "Net-(UEP-DI)") (class "Default")
      (node (ref "P3") (pin "4") (pinfunction "4_4") (pintype "passive"))
      (node (ref "UEP") (pin "3") (pinfunction "DI_3") (pintype "bidirectional"))
    )
    (net (code "32") (name "Net-(UEP-DO)") (class "Default")
      (node (ref "P3") (pin "1") (pinfunction "1_1") (pintype "passive"))
      (node (ref "UEP") (pin "4") (pinfunction "DO_4") (pintype "bidirectional"))
    )
    (net (code "33") (name "Net-(UEP-GND)") (class "Default")
      (node (ref "CE") (pin "2") (pinfunction "2_2") (pintype "passive"))
      (node (ref "P3") (pin "3") (pinfunction "3_3") (pintype "passive"))
      (node (ref "RE") (pin "1") (pinfunction "1_1") (pintype "passive"))
      (node (ref "UEP") (pin "5") (pinfunction "GND_5") (pintype "bidirectional"))
      (node (ref "UEP") (pin "6") (pinfunction "T1_6") (pintype "bidirectional"))
      (node (ref "UEP") (pin "7") (pinfunction "T2_7") (pintype "bidirectional"))
    )
    (net (code "34") (name "Net-(UEP-SK)") (class "Default")
      (node (ref "P3") (pin "5") (pinfunction "5_5") (pintype "passive"))
      (node (ref "UEP") (pin "2") (pinfunction "SK_2") (pintype "bidirectional"))
    )
    (net (code "35") (name "Net-(UEP-VCC)") (class "Default")
      (node (ref "CE") (pin "1") (pinfunction "1_1") (pintype "passive"))
      (node (ref "P3") (pin "2") (pinfunction "2_2") (pintype "passive"))
      (node (ref "UEP") (pin "8") (pinfunction "VCC_8") (pintype "bidirectional"))
    )
    (net (code "36") (name "unconnected-(J1-Pad2)") (class "Default")
      (node (ref "J1") (pin "2") (pinfunction "2_2") (pintype "passive"))
    )
    (net (code "37") (name "unconnected-(J2-BLK-Pad1)") (class "Default")
      (node (ref "J2-BLK") (pin "1") (pinfunction "1_1") (pintype "passive"))
    )
    (net (code "38") (name "unconnected-(J2-WHI-Pad1)") (class "Default")
      (node (ref "J2-WHI") (pin "1") (pinfunction "1_1") (pintype "passive"))
    )
    (net (code "39") (name "unconnected-(P1-Pad1)") (class "Default")
      (node (ref "P1") (pin "1") (pinfunction "1_1") (pintype "passive"))
    )
    (net (code "40") (name "unconnected-(P1-Pad2)") (class "Default")
      (node (ref "P1") (pin "2") (pinfunction "2_2") (pintype "passive"))
    )
    (net (code "41") (name "unconnected-(P1-Pad3)") (class "Default")
      (node (ref "P1") (pin "3") (pinfunction "3_3") (pintype "passive"))
    )
    (net (code "42") (name "unconnected-(U2-C4-Pad06)") (class "Default")
      (node (ref "U2") (pin "06") (pinfunction "C4_06") (pintype "bidirectional"))
    )
    (net (code "43") (name "unconnected-(U2-C5-Pad05)") (class "Default")
      (node (ref "U2") (pin "05") (pinfunction "C5_05") (pintype "bidirectional"))
    )
  )
)
